# main.net
KiCad netlist of a schematic drawn in Altium Designer
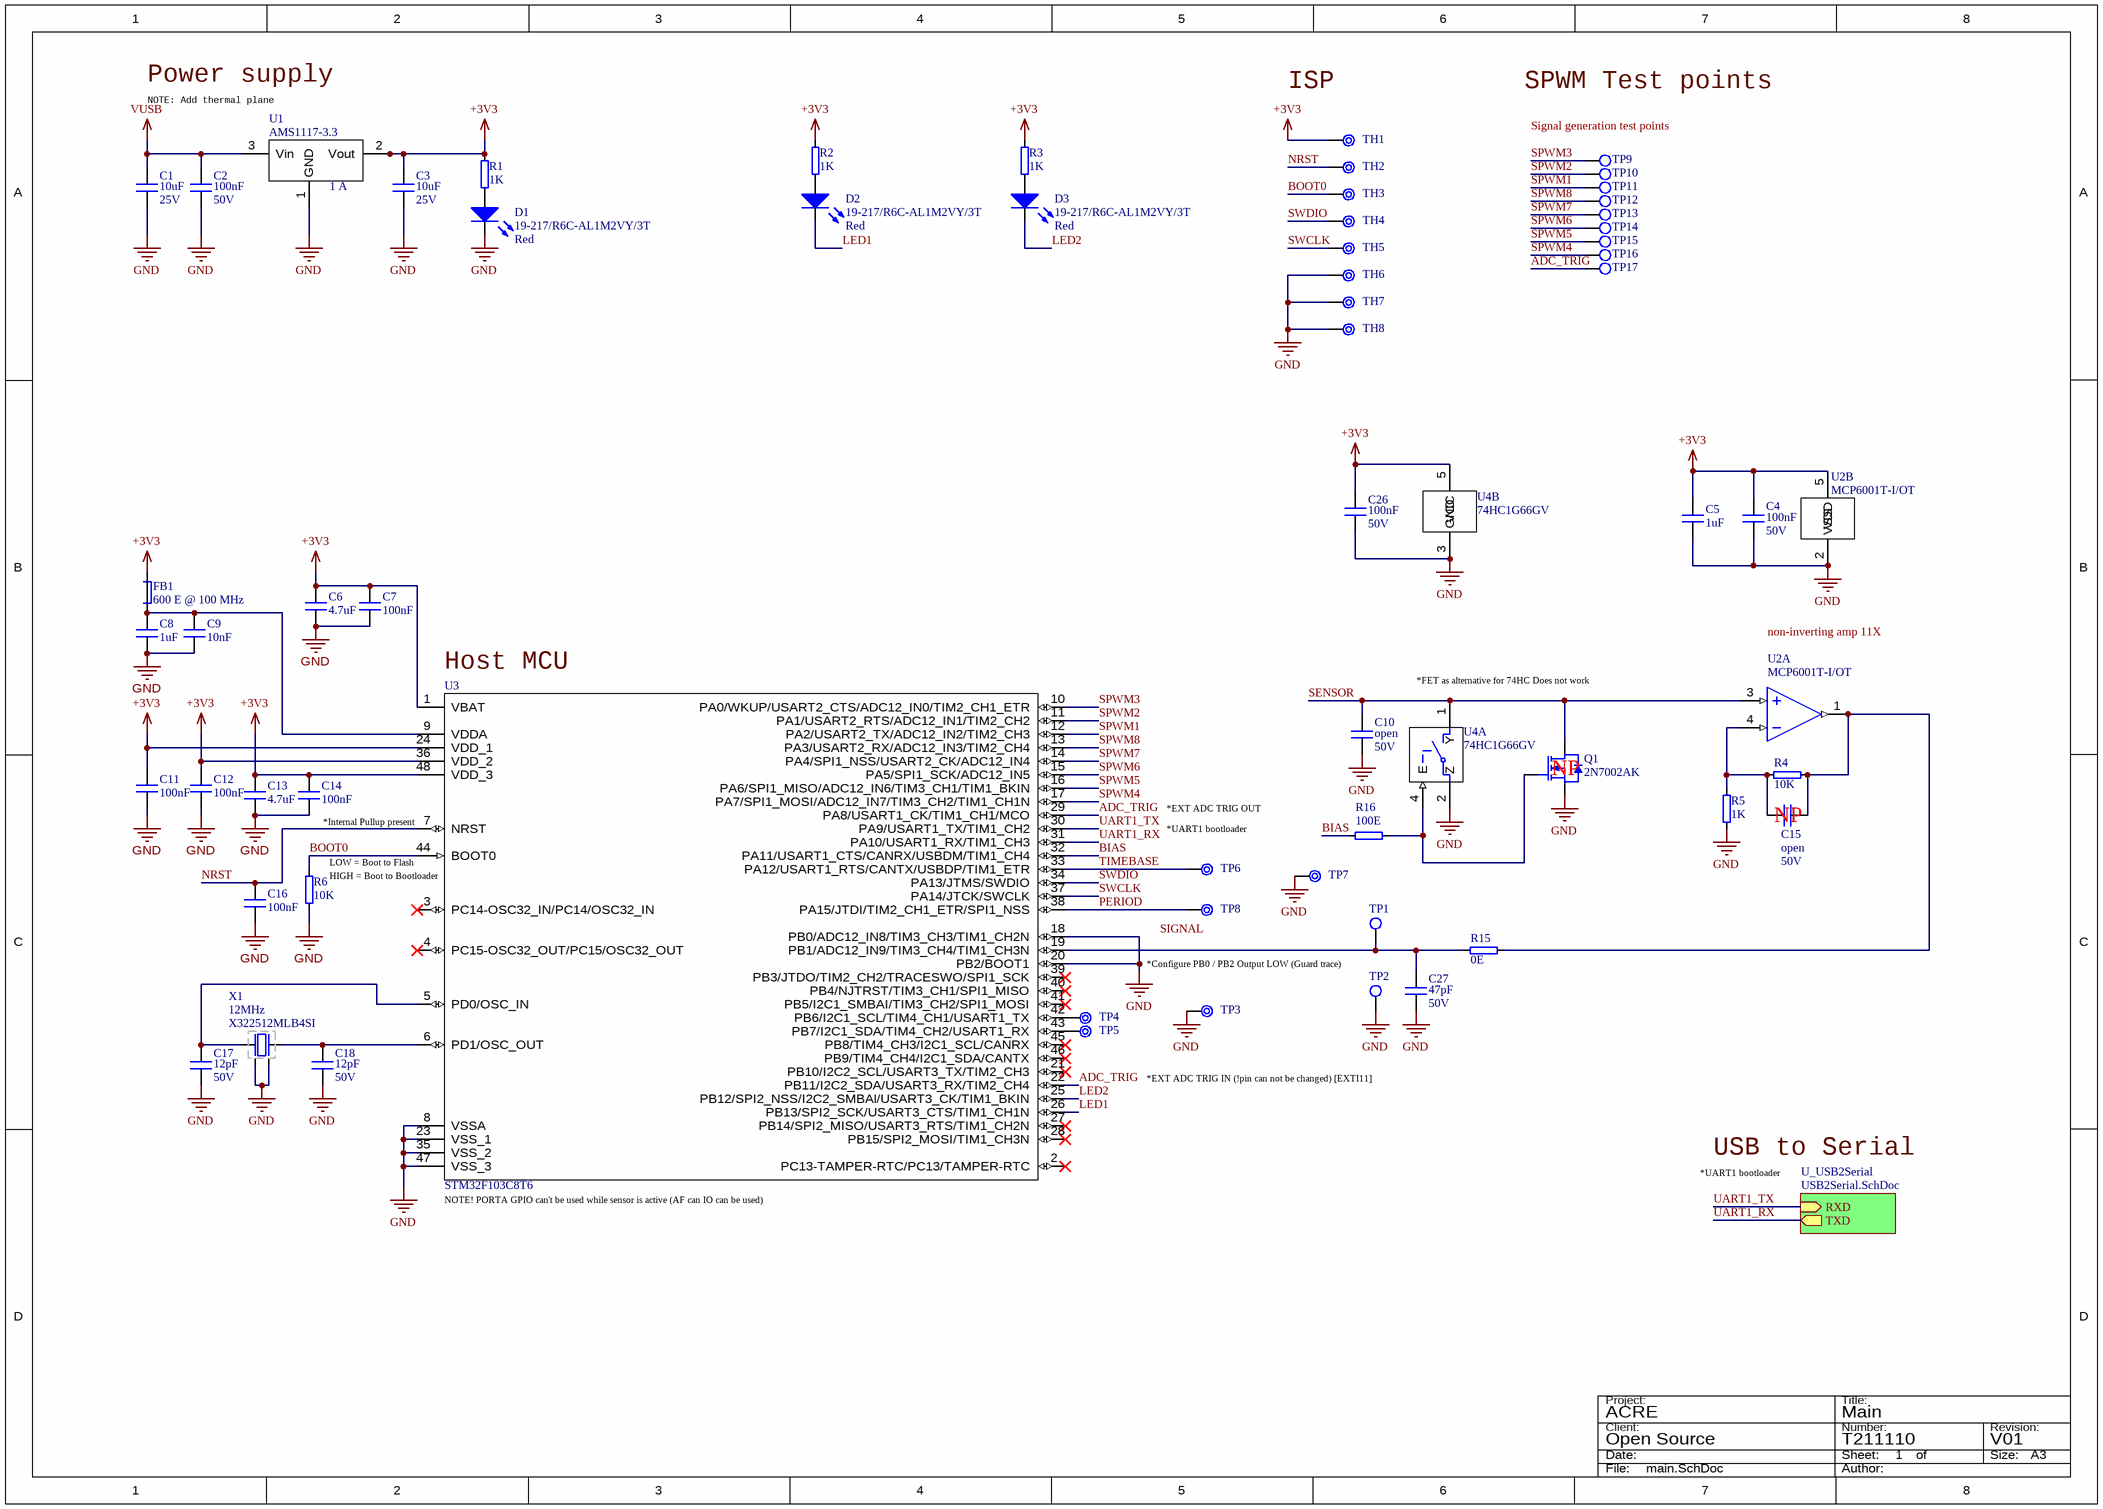
[diagram p0: main.SchDoc]

(export (version "E")
  (design (tool "Eeschema 10.0.6"))
  (components
    (comp (ref "C1")
      (value "10uF")
      (footprint "CAP 1206 3216 IPC MEDIUM")
      (description "10uF ±10% 25V X5R 1206 Multilayer Ceramic Capacitors MLCC - SMD/SMT RoHS")
      (fields
        (field (name "VOLTAGE") "25V")
        (field (name "PART NUMBER") "CL31A106KAHNNNE")
        (field (name "MANUFACTURER") "SAMSUNG")
      )
      (libsource (lib "P") (part "Capacitor"))
    )
    (comp (ref "C2")
      (value "100nF")
      (footprint "CAP 0603 1608 IPC MEDIUM")
      (description "100nF ±10% 50V X7R 0603 Multilayer Ceramic Capacitors MLCC - SMD/SMT RoHS")
      (fields
        (field (name "VOLTAGE") "50V")
        (field (name "PART NUMBER") "C0603B104K500NT")
        (field (name "MANUFACTURER") "TORCH")
      )
      (libsource (lib "P") (part "Capacitor"))
    )
    (comp (ref "C3")
      (value "10uF")
      (footprint "CAP 1206 3216 IPC MEDIUM")
      (description "10uF ±10% 25V X5R 1206 Multilayer Ceramic Capacitors MLCC - SMD/SMT RoHS")
      (fields
        (field (name "VOLTAGE") "25V")
        (field (name "PART NUMBER") "CL31A106KAHNNNE")
        (field (name "MANUFACTURER") "SAMSUNG")
      )
      (libsource (lib "P") (part "Capacitor"))
    )
    (comp (ref "C4")
      (value "100nF")
      (footprint "CAP 0603 1608 IPC MEDIUM")
      (description "100nF ±10% 50V X7R 0603 Multilayer Ceramic Capacitors MLCC - SMD/SMT RoHS")
      (fields
        (field (name "VOLTAGE") "50V")
        (field (name "PART NUMBER") "C0603B104K500NT")
        (field (name "MANUFACTURER") "TORCH")
      )
      (libsource (lib "P") (part "Capacitor"))
    )
    (comp (ref "C5")
      (value "1uF")
      (footprint "CAP 0603 1608 IPC MEDIUM")
      (description "Generic 0603 1608 Capacitor")
      (fields (field (name "VOLTAGE") "16V") (field (name "TOLERANCE") "20%"))
      (libsource (lib "P") (part "Capacitor"))
    )
    (comp (ref "C6")
      (value "4.7uF")
      (footprint "CAP 0603 1608 IPC MEDIUM")
      (description "4.7 µF, 25 V, 0603 [1608 Metric], ± 10%, X5R, GRM Series")
      (fields (field (name "VOLTAGE") "25V") (field (name "TOLERANCE") "10%"))
      (libsource (lib "P") (part "Capacitor"))
    )
    (comp (ref "C7")
      (value "100nF")
      (footprint "CAP 0603 1608 IPC MEDIUM")
      (description "100nF ±10% 50V X7R 0603 Multilayer Ceramic Capacitors MLCC - SMD/SMT RoHS")
      (fields (field (name "VOLTAGE") "50V") (field (name "TOLERANCE") "20%"))
      (libsource (lib "P") (part "Capacitor"))
    )
    (comp (ref "C8")
      (value "1uF")
      (footprint "CAP 0603 1608 IPC MEDIUM")
      (description "Generic 0603 1608 Capacitor")
      (fields (field (name "VOLTAGE") "16V") (field (name "TOLERANCE") "20%"))
      (libsource (lib "P") (part "Capacitor"))
    )
    (comp (ref "C9")
      (value "10nF")
      (footprint "CAP 0603 1608 IPC MEDIUM")
      (description "Generic 0603 1608 Capacitor")
      (fields (field (name "VOLTAGE") "50V") (field (name "TOLERANCE") "10%"))
      (libsource (lib "P") (part "Capacitor"))
    )
    (comp (ref "C10")
      (value "open")
      (footprint "CAP 0603 1608 IPC MEDIUM")
      (description "Capacitor 0603 1608 value undefined")
      (fields
        (field (name "VOLTAGE") "50V")
        (field (name "PART NUMBER") "x")
        (field (name "TOLERANCE") "10%")
      )
      (libsource (lib "P") (part "Capacitor"))
    )
    (comp (ref "C11")
      (value "100nF")
      (footprint "CAP 0603 1608 IPC MEDIUM")
      (description "100nF ±10% 50V X7R 0603 Multilayer Ceramic Capacitors MLCC - SMD/SMT RoHS")
      (fields (field (name "VOLTAGE") "50V") (field (name "TOLERANCE") "20%"))
      (libsource (lib "P") (part "Capacitor"))
    )
    (comp (ref "C12")
      (value "100nF")
      (footprint "CAP 0603 1608 IPC MEDIUM")
      (description "100nF ±10% 50V X7R 0603 Multilayer Ceramic Capacitors MLCC - SMD/SMT RoHS")
      (fields (field (name "VOLTAGE") "50V") (field (name "TOLERANCE") "20%"))
      (libsource (lib "P") (part "Capacitor"))
    )
    (comp (ref "C13")
      (value "4.7uF")
      (footprint "CAP 0603 1608 IPC MEDIUM")
      (description "4.7 µF, 25 V, 0603 [1608 Metric], ± 10%, X5R, GRM Series")
      (fields (field (name "VOLTAGE") "25V") (field (name "TOLERANCE") "10%"))
      (libsource (lib "P") (part "Capacitor"))
    )
    (comp (ref "C14")
      (value "100nF")
      (footprint "CAP 0603 1608 IPC MEDIUM")
      (description "100nF ±10% 50V X7R 0603 Multilayer Ceramic Capacitors MLCC - SMD/SMT RoHS")
      (fields (field (name "VOLTAGE") "50V") (field (name "TOLERANCE") "20%"))
      (libsource (lib "P") (part "Capacitor"))
    )
    (comp (ref "C15")
      (value "open")
      (footprint "CAP 0603 1608 IPC MEDIUM")
      (description "Capacitor 0603 1608 value undefined")
      (fields
        (field (name "VOLTAGE") "50V")
        (field (name "PART NUMBER") "x")
        (field (name "TOLERANCE") "10%")
      )
      (libsource (lib "P") (part "Capacitor"))
    )
    (comp (ref "C16")
      (value "100nF")
      (footprint "CAP 0603 1608 IPC MEDIUM")
      (description "100nF ±10% 50V X7R 0603 Multilayer Ceramic Capacitors MLCC - SMD/SMT RoHS")
      (fields (field (name "VOLTAGE") "50V") (field (name "TOLERANCE") "20%"))
      (libsource (lib "P") (part "Capacitor"))
    )
    (comp (ref "C17")
      (value "12pF")
      (footprint "CAP 0603 1608 IPC MEDIUM")
      (description "12pF ±5% 50V NP0 0603 Multilayer Ceramic Capacitors MLCC - SMD/SMT RoHS")
      (fields
        (field (name "VOLTAGE") "50V")
        (field (name "PART NUMBER") "CC0603JRNPO9BN120")
        (field (name "TOLERANCE") "5%")
      )
      (libsource (lib "P") (part "Capacitor"))
    )
    (comp (ref "C18")
      (value "12pF")
      (footprint "CAP 0603 1608 IPC MEDIUM")
      (description "12pF ±5% 50V NP0 0603 Multilayer Ceramic Capacitors MLCC - SMD/SMT RoHS")
      (fields
        (field (name "VOLTAGE") "50V")
        (field (name "PART NUMBER") "CC0603JRNPO9BN120")
        (field (name "TOLERANCE") "5%")
      )
      (libsource (lib "P") (part "Capacitor"))
    )
    (comp (ref "C26")
      (value "100nF")
      (footprint "CAP 0603 1608 IPC MEDIUM")
      (description "100nF ±10% 50V X7R 0603 Multilayer Ceramic Capacitors MLCC - SMD/SMT RoHS")
      (fields
        (field (name "VOLTAGE") "50V")
        (field (name "PART NUMBER") "C0603B104K500NT")
        (field (name "MANUFACTURER") "TORCH")
      )
      (libsource (lib "P") (part "Capacitor"))
    )
    (comp (ref "C27")
      (value "47pF")
      (footprint "CAP 0603 1608 IPC MEDIUM")
      (description "Generic 0603 1608 Capacitor")
      (fields
        (field (name "VOLTAGE") "50V")
        (field (name "PART NUMBER") "x")
        (field (name "TOLERANCE") "10%")
      )
      (libsource (lib "P") (part "Capacitor"))
    )
    (comp (ref "D1")
      (value "19-217/R6C-AL1M2VY/3T")
      (footprint "19-217 - EVERLIGHT")
      (description "Red 617.5~633.5nm 0603 Light Emitting Diodes (LED) RoHS")
      (fields (field (name "COLOUR") "Red") (field (name "MANUFACTURER") "EVERLIGHT"))
      (libsource (lib "P") (part "LED - [1A 2C]"))
    )
    (comp (ref "D2")
      (value "19-217/R6C-AL1M2VY/3T")
      (footprint "19-217 - EVERLIGHT")
      (description "Red 617.5~633.5nm 0603 Light Emitting Diodes (LED) RoHS")
      (fields (field (name "COLOUR") "Red") (field (name "MANUFACTURER") "EVERLIGHT"))
      (libsource (lib "P") (part "LED - [1A 2C]"))
    )
    (comp (ref "D3")
      (value "19-217/R6C-AL1M2VY/3T")
      (footprint "19-217 - EVERLIGHT")
      (description "Red 617.5~633.5nm 0603 Light Emitting Diodes (LED) RoHS")
      (fields (field (name "COLOUR") "Red") (field (name "MANUFACTURER") "EVERLIGHT"))
      (libsource (lib "P") (part "LED - [1A 2C]"))
    )
    (comp (ref "FB1")
      (value "600 E @ 100 MHz")
      (footprint "FB 0603 1608 IPC MEDIUM - Murata")
      (description "Ferrite Bead, 0603 [1608 Metric], 600 ohm, 500 mA, BLM18A Series, 0.38 ohm, ± 25%")
      (fields (field (name "PART NUMBER") "BLM18AG601SN1D") (field (name "MANUFACTURER") "MURATA"))
      (libsource (lib "P") (part "Ferrite bead"))
    )
    (comp (ref "Q1")
      (value "2N7002AK")
      (footprint "SOT23-3 IPC MEDIUM - NEXPERIA")
      (description "Power MOSFET, N Channel, 60 V, 190 mA, 3 ohm, SOT-23 TO-236AB")
      (fields (field (name "MANUFACTURER") "NEXPERIA"))
      (libsource (lib "P") (part "FET N-Channel [1G 2S 3D]"))
    )
    (comp (ref "R1")
      (value "1K")
      (footprint "RES 0603 1608 IPC MEDIUM")
      (description "1kΩ ±1% 0.1W ±100ppm/℃ 0603 Chip Resistor - Surface Mount RoHS")
      (fields (field (name "PART NUMBER") "RC0603FR-071KL") (field (name "MANUFACTURER") "YAGEO"))
      (libsource (lib "") (part "Resistor_1"))
    )
    (comp (ref "R2")
      (value "1K")
      (footprint "RES 0603 1608 IPC MEDIUM")
      (description "1kΩ ±1% 0.1W ±100ppm/℃ 0603 Chip Resistor - Surface Mount RoHS")
      (fields (field (name "PART NUMBER") "RC0603FR-071KL") (field (name "MANUFACTURER") "YAGEO"))
      (libsource (lib "") (part "Resistor_1"))
    )
    (comp (ref "R3")
      (value "1K")
      (footprint "RES 0603 1608 IPC MEDIUM")
      (description "1kΩ ±1% 0.1W ±100ppm/℃ 0603 Chip Resistor - Surface Mount RoHS")
      (fields (field (name "PART NUMBER") "RC0603FR-071KL") (field (name "MANUFACTURER") "YAGEO"))
      (libsource (lib "") (part "Resistor_1"))
    )
    (comp (ref "R4")
      (value "10K")
      (footprint "RES 0603 1608 IPC MEDIUM")
      (description "10kΩ ±1% 0.1W ±100ppm/℃ 0603 Chip Resistor - Surface Mount RoHS")
      (fields (field (name "PART NUMBER") "RC0603FR-0710KL") (field (name "MANUFACTURER") "YAGEO"))
      (libsource (lib "") (part "Resistor_2"))
    )
    (comp (ref "R5")
      (value "1K")
      (footprint "RES 0603 1608 IPC MEDIUM")
      (description "1kΩ ±1% 0.1W ±100ppm/℃ 0603 Chip Resistor - Surface Mount RoHS")
      (fields (field (name "PART NUMBER") "RC0603FR-071KL") (field (name "MANUFACTURER") "YAGEO"))
      (libsource (lib "") (part "Resistor_1"))
    )
    (comp (ref "R6")
      (value "10K")
      (footprint "RES 0603 1608 IPC MEDIUM")
      (description "10kΩ ±1% 0.1W ±100ppm/℃ 0603 Chip Resistor - Surface Mount RoHS")
      (fields (field (name "VOLTAGE") "75V") (field (name "POWER") "100mW"))
      (libsource (lib "P") (part "Resistor"))
    )
    (comp (ref "R15")
      (value "0E")
      (footprint "RES 0603 1608 IPC MEDIUM")
      (description "0Ω ±1.0% 1/10W Thick Film Resistors 75V -55℃~+155℃ 0603 Chip Resistor - Surface Mount RoHS")
      (fields (field (name "PART NUMBER") "RC0603FR-070RL") (field (name "MANUFACTURER") "YAGEO"))
      (libsource (lib "") (part "Resistor_2"))
    )
    (comp (ref "R16")
      (value "100E")
      (footprint "RES 0603 1608 IPC MEDIUM")
      (fields
        (field (name "PART NUMBER") "RC0603FR-07100RL")
        (field (name "VOLTAGE") "75V")
        (field (name "POWER") "100mW")
      )
      (libsource (lib "") (part "Resistor_2"))
    )
    (comp (ref "TH1")
      (value "~")
      (footprint "Test Header H1D1.6")
      (description "Octagonal THT H1D1.6mm test header")
      (libsource (lib "P") (part "Test Header"))
    )
    (comp (ref "TH2")
      (value "~")
      (footprint "Test Header H1D1.6")
      (description "Octagonal THT H1D1.6mm test header")
      (libsource (lib "P") (part "Test Header"))
    )
    (comp (ref "TH3")
      (value "~")
      (footprint "Test Header H1D1.6")
      (description "Octagonal THT H1D1.6mm test header")
      (libsource (lib "P") (part "Test Header"))
    )
    (comp (ref "TH4")
      (value "~")
      (footprint "Test Header H1D1.6")
      (description "Octagonal THT H1D1.6mm test header")
      (libsource (lib "P") (part "Test Header"))
    )
    (comp (ref "TH5")
      (value "~")
      (footprint "Test Header H1D1.6")
      (description "Octagonal THT H1D1.6mm test header")
      (libsource (lib "P") (part "Test Header"))
    )
    (comp (ref "TH6")
      (value "~")
      (footprint "Test Header H1D1.6")
      (description "Octagonal THT H1D1.6mm test header")
      (libsource (lib "P") (part "Test Header"))
    )
    (comp (ref "TH7")
      (value "~")
      (footprint "Test Header H1D1.6")
      (description "Octagonal THT H1D1.6mm test header")
      (libsource (lib "P") (part "Test Header"))
    )
    (comp (ref "TH8")
      (value "~")
      (footprint "Test Header H1D1.6")
      (description "Octagonal THT H1D1.6mm test header")
      (libsource (lib "P") (part "Test Header"))
    )
    (comp (ref "TP1")
      (value "0.8mm")
      (footprint "TEST POINT 0.8MM")
      (description "Round 0.8mm testpoint")
      (libsource (lib "P") (part "Test Point"))
    )
    (comp (ref "TP2")
      (value "0.8mm")
      (footprint "TEST POINT 0.8MM")
      (description "Round 0.8mm testpoint")
      (libsource (lib "P") (part "Test Point"))
    )
    (comp (ref "TP3")
      (value "~")
      (footprint "Test Header H1D1.6")
      (description "Octagonal THT H1D1.6mm test header")
      (libsource (lib "P") (part "Test Header"))
    )
    (comp (ref "TP4")
      (value "~")
      (footprint "Test Header H1D1.6")
      (description "Octagonal THT H1D1.6mm test header")
      (libsource (lib "P") (part "Test Header"))
    )
    (comp (ref "TP5")
      (value "~")
      (footprint "Test Header H1D1.6")
      (description "Octagonal THT H1D1.6mm test header")
      (libsource (lib "P") (part "Test Header"))
    )
    (comp (ref "TP6")
      (value "~")
      (footprint "Test Header H1D1.6")
      (description "Octagonal THT H1D1.6mm test header")
      (libsource (lib "P") (part "Test Header"))
    )
    (comp (ref "TP7")
      (value "~")
      (footprint "Test Header H1D1.6")
      (description "Octagonal THT H1D1.6mm test header")
      (libsource (lib "P") (part "Test Header"))
    )
    (comp (ref "TP8")
      (value "~")
      (footprint "Test Header H1D1.6")
      (description "Octagonal THT H1D1.6mm test header")
      (libsource (lib "P") (part "Test Header"))
    )
    (comp (ref "TP9")
      (value "0.5mm")
      (footprint "TEST POINT 0.5MM")
      (description "Round 0.5mm testpoint")
      (libsource (lib "P") (part "Test Point"))
    )
    (comp (ref "TP10")
      (value "0.5mm")
      (footprint "TEST POINT 0.5MM")
      (description "Round 0.5mm testpoint")
      (libsource (lib "P") (part "Test Point"))
    )
    (comp (ref "TP11")
      (value "0.5mm")
      (footprint "TEST POINT 0.5MM")
      (description "Round 0.5mm testpoint")
      (libsource (lib "P") (part "Test Point"))
    )
    (comp (ref "TP12")
      (value "0.5mm")
      (footprint "TEST POINT 0.5MM")
      (description "Round 0.5mm testpoint")
      (libsource (lib "P") (part "Test Point"))
    )
    (comp (ref "TP13")
      (value "0.5mm")
      (footprint "TEST POINT 0.5MM")
      (description "Round 0.5mm testpoint")
      (libsource (lib "P") (part "Test Point"))
    )
    (comp (ref "TP14")
      (value "0.5mm")
      (footprint "TEST POINT 0.5MM")
      (description "Round 0.5mm testpoint")
      (libsource (lib "P") (part "Test Point"))
    )
    (comp (ref "TP15")
      (value "0.5mm")
      (footprint "TEST POINT 0.5MM")
      (description "Round 0.5mm testpoint")
      (libsource (lib "P") (part "Test Point"))
    )
    (comp (ref "TP16")
      (value "0.5mm")
      (footprint "TEST POINT 0.5MM")
      (description "Round 0.5mm testpoint")
      (libsource (lib "P") (part "Test Point"))
    )
    (comp (ref "TP17")
      (value "0.5mm")
      (footprint "TEST POINT 0.5MM")
      (description "Round 0.5mm testpoint")
      (libsource (lib "P") (part "Test Point"))
    )
    (comp (ref "U1")
      (value "AMS1117-3.3")
      (footprint "SOT223 IPC MEDIUM - UMW")
      (description "LDO 3.3V 1A 18V")
      (fields (field (name "MANUFACTURER") "UMW") (field (name "IOUT") "1 A"))
      (libsource (lib "P") (part "AMS1117-3.3 - UMW"))
    )
    (comp (ref "U2")
      (value "MCP6001T-I/OT")
      (footprint "SOT23-5 IPC MEDIUM - MICROCHIP")
      (description "Operational Amplifier, Single, 1 Amplifier, 1 MHz, 0.6 V/µs, 1.8V to 6V, SOT-23, 5 Pins")
      (fields (field (name "MANUFACTURER") "MICROCHIP"))
      (libsource (lib "") (part "MCP6001T-I OT - MICROCHIP_1"))
    )
    (comp (ref "U3")
      (value "STM32F103C8T6")
      (footprint "LQFP48 IPC MEDIUM - STMICROELECTRONICS")
      (description "ARM Microcontroller, Motor Control, STM32 Family STM32F1 Series Microcontrollers, ARM Cortex-M3")
      (fields (field (name "MANUFACTURER") "STMICROELECTRONICS"))
      (libsource (lib "P") (part "STM32F103C8T6 - STMICROELECTRONICS"))
    )
    (comp (ref "U4")
      (value "74HC1G66GV")
      (footprint "SOT753 IPC MEDIUM - NEXPERIA")
      (description "Analogue Switch, SPST, 1 Channels, 50 ohm, 2V to 9V, TSOP, 5 Pins")
      (fields (field (name "MANUFACTURER") "NEXPERIA"))
      (libsource (lib "P") (part "74HC1G66GV - NEXPERIA"))
    )
    (comp (ref "X1")
      (value "X322512MLB4SI")
      (footprint "X322512MLB4SI - YXC")
      (description "12MHz ±10ppm 9pF 80Ω SMD-3225_4P Crystals RoHS")
      (fields (field (name "FREQUENCY") "12MHz") (field (name "MANUFACTURER") "YXC"))
      (libsource (lib "P") (part "Crystal in1 gnd2 out3 gnd4"))
    )
  )
  (nets
    (net (code "1") (name "+3V3") (class "Default")
      (node (ref "C11") (pin "1") (pinfunction "1_1") (pintype "passive"))
      (node (ref "C12") (pin "1") (pinfunction "1_1") (pintype "passive"))
      (node (ref "C13") (pin "1") (pinfunction "1_1") (pintype "passive"))
      (node (ref "C14") (pin "1") (pinfunction "1_1") (pintype "passive"))
      (node (ref "C26") (pin "1") (pinfunction "1_1") (pintype "passive"))
      (node (ref "C3") (pin "1") (pinfunction "1_1") (pintype "passive"))
      (node (ref "C4") (pin "1") (pinfunction "1_1") (pintype "passive"))
      (node (ref "C5") (pin "1") (pinfunction "1_1") (pintype "passive"))
      (node (ref "C6") (pin "1") (pinfunction "1_1") (pintype "passive"))
      (node (ref "C7") (pin "1") (pinfunction "1_1") (pintype "passive"))
      (node (ref "FB1") (pin "1") (pinfunction "1_1") (pintype "passive"))
      (node (ref "R1") (pin "2") (pinfunction "2_2") (pintype "passive"))
      (node (ref "R2") (pin "2") (pinfunction "2_2") (pintype "passive"))
      (node (ref "R3") (pin "2") (pinfunction "2_2") (pintype "passive"))
      (node (ref "TH1") (pin "1") (pintype "passive"))
      (node (ref "U1") (pin "2") (pinfunction "Vout_2") (pintype "power_in"))
      (node (ref "U1") (pin "4") (pinfunction "Vout_4") (pintype "power_in"))
      (node (ref "U2") (pin "5") (pinfunction "VDD_5") (pintype "power_in"))
      (node (ref "U3") (pin "1") (pinfunction "VBAT_1") (pintype "power_in"))
      (node (ref "U3") (pin "24") (pinfunction "VDD_1_24") (pintype "power_in"))
      (node (ref "U3") (pin "36") (pinfunction "VDD_2_36") (pintype "power_in"))
      (node (ref "U3") (pin "48") (pinfunction "VDD_3_48") (pintype "power_in"))
      (node (ref "U4") (pin "5") (pinfunction "VCC_5") (pintype "power_in"))
    )
    (net (code "2") (name "/ADC_TRIG") (class "Default")
      (node (ref "TP17") (pin "1") (pintype "passive"))
      (node (ref "U3") (pin "22") (pinfunction "PB11/I2C2_SDA/USART3_RX/TIM2_CH4_22") (pintype "bidirectional"))
      (node (ref "U3") (pin "29") (pinfunction "PA8/USART1_CK/TIM1_CH1/MCO_29") (pintype "bidirectional"))
    )
    (net (code "3") (name "/BIAS") (class "Default")
      (node (ref "R16") (pin "1") (pinfunction "1_1") (pintype "passive"))
      (node (ref "U3") (pin "32") (pinfunction "PA11/USART1_CTS/CANRX/USBDM/TIM1_CH4_32") (pintype "bidirectional"))
    )
    (net (code "4") (name "/BOOT0") (class "Default")
      (node (ref "R6") (pin "1") (pinfunction "1_1") (pintype "passive"))
      (node (ref "TH3") (pin "1") (pintype "passive"))
      (node (ref "U3") (pin "44") (pinfunction "BOOT0_44") (pintype "input"))
    )
    (net (code "5") (name "/LED1") (class "Default")
      (node (ref "D2") (pin "2") (pinfunction "C_2") (pintype "passive"))
      (node (ref "U3") (pin "26") (pinfunction "PB13/SPI2_SCK/USART3_CTS/TIM1_CH1N_26") (pintype "bidirectional"))
    )
    (net (code "6") (name "/LED2") (class "Default")
      (node (ref "D3") (pin "2") (pinfunction "C_2") (pintype "passive"))
      (node (ref "U3") (pin "25") (pinfunction "PB12/SPI2_NSS/I2C2_SMBAl/USART3_CK/TIM1_BKIN_25") (pintype "bidirectional"))
    )
    (net (code "7") (name "/NRST") (class "Default")
      (node (ref "C16") (pin "1") (pinfunction "1_1") (pintype "passive"))
      (node (ref "TH2") (pin "1") (pintype "passive"))
      (node (ref "U3") (pin "7") (pinfunction "NRST_7") (pintype "bidirectional"))
    )
    (net (code "8") (name "/PERIOD") (class "Default")
      (node (ref "TP8") (pin "1") (pintype "passive"))
      (node (ref "U3") (pin "38") (pinfunction "PA15/JTDI/TIM2_CH1_ETR/SPI1_NSS_38") (pintype "bidirectional"))
    )
    (net (code "9") (name "/SENSOR") (class "Default")
      (node (ref "C10") (pin "1") (pinfunction "1_1") (pintype "passive"))
      (node (ref "Q1") (pin "3") (pinfunction "D_3") (pintype "passive"))
      (node (ref "U2") (pin "3") (pinfunction "VIN+_3") (pintype "input"))
      (node (ref "U4") (pin "1") (pinfunction "Y_1") (pintype "passive"))
    )
    (net (code "11") (name "/SPWM1") (class "Default")
      (node (ref "TP11") (pin "1") (pintype "passive"))
      (node (ref "U3") (pin "12") (pinfunction "PA2/USART2_TX/ADC12_IN2/TIM2_CH3_12") (pintype "bidirectional"))
    )
    (net (code "12") (name "/SPWM2") (class "Default")
      (node (ref "TP10") (pin "1") (pintype "passive"))
      (node (ref "U3") (pin "11") (pinfunction "PA1/USART2_RTS/ADC12_IN1/TIM2_CH2_11") (pintype "bidirectional"))
    )
    (net (code "13") (name "/SPWM3") (class "Default")
      (node (ref "TP9") (pin "1") (pintype "passive"))
      (node (ref "U3") (pin "10") (pinfunction "PA0/WKUP/USART2_CTS/ADC12_IN0/TIM2_CH1_ETR_10") (pintype "bidirectional"))
    )
    (net (code "14") (name "/SPWM4") (class "Default")
      (node (ref "TP16") (pin "1") (pintype "passive"))
      (node (ref "U3") (pin "17") (pinfunction "PA7/SPI1_MOSI/ADC12_IN7/TIM3_CH2/TIM1_CH1N_17") (pintype "bidirectional"))
    )
    (net (code "15") (name "/SPWM5") (class "Default")
      (node (ref "TP15") (pin "1") (pintype "passive"))
      (node (ref "U3") (pin "16") (pinfunction "PA6/SPI1_MISO/ADC12_IN6/TIM3_CH1/TIM1_BKIN_16") (pintype "bidirectional"))
    )
    (net (code "16") (name "/SPWM6") (class "Default")
      (node (ref "TP14") (pin "1") (pintype "passive"))
      (node (ref "U3") (pin "15") (pinfunction "PA5/SPI1_SCK/ADC12_IN5_15") (pintype "bidirectional"))
    )
    (net (code "17") (name "/SPWM7") (class "Default")
      (node (ref "TP13") (pin "1") (pintype "passive"))
      (node (ref "U3") (pin "14") (pinfunction "PA4/SPI1_NSS/USART2_CK/ADC12_IN4_14") (pintype "bidirectional"))
    )
    (net (code "18") (name "/SPWM8") (class "Default")
      (node (ref "TP12") (pin "1") (pintype "passive"))
      (node (ref "U3") (pin "13") (pinfunction "PA3/USART2_RX/ADC12_IN3/TIM2_CH4_13") (pintype "bidirectional"))
    )
    (net (code "19") (name "/SWCLK") (class "Default")
      (node (ref "TH5") (pin "1") (pintype "passive"))
      (node (ref "U3") (pin "37") (pinfunction "PA14/JTCK/SWCLK_37") (pintype "bidirectional"))
    )
    (net (code "20") (name "/SWDIO") (class "Default")
      (node (ref "TH4") (pin "1") (pintype "passive"))
      (node (ref "U3") (pin "34") (pinfunction "PA13/JTMS/SWDIO_34") (pintype "bidirectional"))
    )
    (net (code "21") (name "/TIMEBASE") (class "Default")
      (node (ref "TP6") (pin "1") (pintype "passive"))
      (node (ref "U3") (pin "33") (pinfunction "PA12/USART1_RTS/CANTX/USBDP/TIM1_ETR_33") (pintype "bidirectional"))
    )
    (net (code "22") (name "/UART1_RX") (class "Default")
      (node (ref "U3") (pin "31") (pinfunction "PA10/USART1_RX/TIM1_CH3_31") (pintype "bidirectional"))
    )
    (net (code "23") (name "/UART1_TX") (class "Default")
      (node (ref "U3") (pin "30") (pinfunction "PA9/USART1_TX/TIM1_CH2_30") (pintype "bidirectional"))
    )
    (net (code "24") (name "GND") (class "Default")
      (node (ref "C1") (pin "2") (pinfunction "2_2") (pintype "passive"))
      (node (ref "C10") (pin "2") (pinfunction "2_2") (pintype "passive"))
      (node (ref "C11") (pin "2") (pinfunction "2_2") (pintype "passive"))
      (node (ref "C12") (pin "2") (pinfunction "2_2") (pintype "passive"))
      (node (ref "C13") (pin "2") (pinfunction "2_2") (pintype "passive"))
      (node (ref "C14") (pin "2") (pinfunction "2_2") (pintype "passive"))
      (node (ref "C16") (pin "2") (pinfunction "2_2") (pintype "passive"))
      (node (ref "C17") (pin "2") (pinfunction "2_2") (pintype "passive"))
      (node (ref "C18") (pin "2") (pinfunction "2_2") (pintype "passive"))
      (node (ref "C2") (pin "2") (pinfunction "2_2") (pintype "passive"))
      (node (ref "C26") (pin "2") (pinfunction "2_2") (pintype "passive"))
      (node (ref "C27") (pin "2") (pinfunction "2_2") (pintype "passive"))
      (node (ref "C3") (pin "2") (pinfunction "2_2") (pintype "passive"))
      (node (ref "C4") (pin "2") (pinfunction "2_2") (pintype "passive"))
      (node (ref "C5") (pin "2") (pinfunction "2_2") (pintype "passive"))
      (node (ref "C6") (pin "2") (pinfunction "2_2") (pintype "passive"))
      (node (ref "C7") (pin "2") (pinfunction "2_2") (pintype "passive"))
      (node (ref "C8") (pin "2") (pinfunction "2_2") (pintype "passive"))
      (node (ref "C9") (pin "2") (pinfunction "2_2") (pintype "passive"))
      (node (ref "D1") (pin "2") (pinfunction "C_2") (pintype "passive"))
      (node (ref "Q1") (pin "2") (pinfunction "S_2") (pintype "passive"))
      (node (ref "R5") (pin "1") (pinfunction "1_1") (pintype "passive"))
      (node (ref "R6") (pin "2") (pinfunction "2_2") (pintype "passive"))
      (node (ref "TH6") (pin "1") (pintype "passive"))
      (node (ref "TH7") (pin "1") (pintype "passive"))
      (node (ref "TH8") (pin "1") (pintype "passive"))
      (node (ref "TP2") (pin "1") (pintype "passive"))
      (node (ref "TP3") (pin "1") (pintype "passive"))
      (node (ref "TP7") (pin "1") (pintype "passive"))
      (node (ref "U1") (pin "1") (pinfunction "GND_1") (pintype "power_in"))
      (node (ref "U2") (pin "2") (pinfunction "VSS_2") (pintype "power_in"))
      (node (ref "U3") (pin "18") (pinfunction "PB0/ADC12_IN8/TIM3_CH3/TIM1_CH2N_18") (pintype "bidirectional"))
      (node (ref "U3") (pin "20") (pinfunction "PB2/BOOT1_20") (pintype "bidirectional"))
      (node (ref "U3") (pin "23") (pinfunction "VSS_1_23") (pintype "power_in"))
      (node (ref "U3") (pin "35") (pinfunction "VSS_2_35") (pintype "power_in"))
      (node (ref "U3") (pin "47") (pinfunction "VSS_3_47") (pintype "power_in"))
      (node (ref "U3") (pin "8") (pinfunction "VSSA_8") (pintype "power_in"))
      (node (ref "U4") (pin "2") (pinfunction "Z_2") (pintype "passive"))
      (node (ref "U4") (pin "3") (pinfunction "GND_3") (pintype "power_in"))
      (node (ref "X1") (pin "2") (pinfunction "GND_2") (pintype "passive"))
      (node (ref "X1") (pin "4") (pinfunction "GND_4") (pintype "passive"))
    )
    (net (code "25") (name "Net-(D1-A)") (class "Default")
      (node (ref "D1") (pin "1") (pinfunction "A_1") (pintype "passive"))
      (node (ref "R1") (pin "1") (pinfunction "1_1") (pintype "passive"))
    )
    (net (code "26") (name "Net-(D2-A)") (class "Default")
      (node (ref "D2") (pin "1") (pinfunction "A_1") (pintype "passive"))
      (node (ref "R2") (pin "1") (pinfunction "1_1") (pintype "passive"))
    )
    (net (code "27") (name "Net-(D3-A)") (class "Default")
      (node (ref "D3") (pin "1") (pinfunction "A_1") (pintype "passive"))
      (node (ref "R3") (pin "1") (pinfunction "1_1") (pintype "passive"))
    )
    (net (code "28") (name "Net-(Q1-G)") (class "Default")
      (node (ref "Q1") (pin "1") (pinfunction "G_1") (pintype "passive"))
      (node (ref "R16") (pin "2") (pinfunction "2_2") (pintype "passive"))
      (node (ref "U4") (pin "4") (pinfunction "E_4") (pintype "input"))
    )
    (net (code "29") (name "Net-(U2A-VIN-)") (class "Default")
      (node (ref "C15") (pin "1") (pinfunction "1_1") (pintype "passive"))
      (node (ref "R4") (pin "1") (pinfunction "1_1") (pintype "passive"))
      (node (ref "R5") (pin "2") (pinfunction "2_2") (pintype "passive"))
      (node (ref "U2") (pin "4") (pinfunction "VIN-_4") (pintype "input"))
    )
    (net (code "30") (name "Net-(U2A-VOUT)") (class "Default")
      (node (ref "C15") (pin "2") (pinfunction "2_2") (pintype "passive"))
      (node (ref "R15") (pin "2") (pinfunction "2_2") (pintype "passive"))
      (node (ref "R4") (pin "2") (pinfunction "2_2") (pintype "passive"))
      (node (ref "U2") (pin "1") (pinfunction "VOUT_1") (pintype "output"))
    )
    (net (code "31") (name "Net-(U3-PB1{slash}ADC12_IN9{slash}TIM3_CH4{slash}TIM1_CH3N)") (class "Default")
      (node (ref "C27") (pin "1") (pinfunction "1_1") (pintype "passive"))
      (node (ref "R15") (pin "1") (pinfunction "1_1") (pintype "passive"))
      (node (ref "TP1") (pin "1") (pintype "passive"))
      (node (ref "U3") (pin "19") (pinfunction "PB1/ADC12_IN9/TIM3_CH4/TIM1_CH3N_19") (pintype "bidirectional"))
    )
    (net (code "32") (name "Net-(U3-PB6{slash}I2C1_SCL{slash}TIM4_CH1{slash}USART1_TX)") (class "Default")
      (node (ref "TP4") (pin "1") (pintype "passive"))
      (node (ref "U3") (pin "42") (pinfunction "PB6/I2C1_SCL/TIM4_CH1/USART1_TX_42") (pintype "bidirectional"))
    )
    (net (code "33") (name "Net-(U3-PB7{slash}I2C1_SDA{slash}TIM4_CH2{slash}USART1_RX)") (class "Default")
      (node (ref "TP5") (pin "1") (pintype "passive"))
      (node (ref "U3") (pin "43") (pinfunction "PB7/I2C1_SDA/TIM4_CH2/USART1_RX_43") (pintype "bidirectional"))
    )
    (net (code "34") (name "Net-(U3-PD0{slash}OSC_IN)") (class "Default")
      (node (ref "C17") (pin "1") (pinfunction "1_1") (pintype "passive"))
      (node (ref "U3") (pin "5") (pinfunction "PD0/OSC_IN_5") (pintype "bidirectional"))
      (node (ref "X1") (pin "1") (pinfunction "in_1") (pintype "passive"))
    )
    (net (code "35") (name "Net-(U3-PD1{slash}OSC_OUT)") (class "Default")
      (node (ref "C18") (pin "1") (pinfunction "1_1") (pintype "passive"))
      (node (ref "U3") (pin "6") (pinfunction "PD1/OSC_OUT_6") (pintype "bidirectional"))
      (node (ref "X1") (pin "3") (pinfunction "out_3") (pintype "passive"))
    )
    (net (code "36") (name "Net-(U3-VDDA)") (class "Default")
      (node (ref "C8") (pin "1") (pinfunction "1_1") (pintype "passive"))
      (node (ref "C9") (pin "1") (pinfunction "1_1") (pintype "passive"))
      (node (ref "FB1") (pin "2") (pinfunction "2_2") (pintype "passive"))
      (node (ref "U3") (pin "9") (pinfunction "VDDA_9") (pintype "power_in"))
    )
    (net (code "37") (name "VUSB") (class "Default")
      (node (ref "C1") (pin "1") (pinfunction "1_1") (pintype "passive"))
      (node (ref "C2") (pin "1") (pinfunction "1_1") (pintype "passive"))
      (node (ref "U1") (pin "3") (pinfunction "Vin_3") (pintype "power_in"))
    )
    (net (code "38") (name "unconnected-(U3-PB3{slash}JTDO{slash}TIM2_CH2{slash}TRACESWO{slash}SPI1_SCK-Pad39)") (class "Default")
      (node (ref "U3") (pin "39") (pinfunction "PB3/JTDO/TIM2_CH2/TRACESWO/SPI1_SCK_39") (pintype "bidirectional+no_connect"))
    )
    (net (code "39") (name "unconnected-(U3-PB4{slash}NJTRST{slash}TIM3_CH1{slash}SPI1_MISO-Pad40)") (class "Default")
      (node (ref "U3") (pin "40") (pinfunction "PB4/NJTRST/TIM3_CH1/SPI1_MISO_40") (pintype "bidirectional+no_connect"))
    )
    (net (code "40") (name "unconnected-(U3-PB5{slash}I2C1_SMBAI{slash}TIM3_CH2{slash}SPI1_MOSI-Pad41)") (class "Default")
      (node (ref "U3") (pin "41") (pinfunction "PB5/I2C1_SMBAI/TIM3_CH2/SPI1_MOSI_41") (pintype "bidirectional+no_connect"))
    )
    (net (code "41") (name "unconnected-(U3-PB8{slash}TIM4_CH3{slash}I2C1_SCL{slash}CANRX-Pad45)") (class "Default")
      (node (ref "U3") (pin "45") (pinfunction "PB8/TIM4_CH3/I2C1_SCL/CANRX_45") (pintype "bidirectional+no_connect"))
    )
    (net (code "42") (name "unconnected-(U3-PB9{slash}TIM4_CH4{slash}I2C1_SDA{slash}CANTX-Pad46)") (class "Default")
      (node (ref "U3") (pin "46") (pinfunction "PB9/TIM4_CH4/I2C1_SDA/CANTX_46") (pintype "bidirectional+no_connect"))
    )
    (net (code "43") (name "unconnected-(U3-PB10{slash}I2C2_SCL{slash}USART3_TX{slash}TIM2_CH3-Pad21)") (class "Default")
      (node (ref "U3") (pin "21") (pinfunction "PB10/I2C2_SCL/USART3_TX/TIM2_CH3_21") (pintype "bidirectional+no_connect"))
    )
    (net (code "44") (name "unconnected-(U3-PB14{slash}SPI2_MISO{slash}USART3_RTS{slash}TIM1_CH2N-Pad27)") (class "Default")
      (node (ref "U3") (pin "27") (pinfunction "PB14/SPI2_MISO/USART3_RTS/TIM1_CH2N_27") (pintype "bidirectional+no_connect"))
    )
    (net (code "45") (name "unconnected-(U3-PB15{slash}SPI2_MOSI{slash}TIM1_CH3N-Pad28)") (class "Default")
      (node (ref "U3") (pin "28") (pinfunction "PB15/SPI2_MOSI/TIM1_CH3N_28") (pintype "bidirectional+no_connect"))
    )
    (net (code "46") (name "unconnected-(U3-PC13-TAMPER-RTC{slash}PC13{slash}TAMPER-RTC-Pad2)") (class "Default")
      (node (ref "U3") (pin "2") (pinfunction "PC13-TAMPER-RTC/PC13/TAMPER-RTC_2") (pintype "bidirectional+no_connect"))
    )
    (net (code "47") (name "unconnected-(U3-PC14-OSC32_IN{slash}PC14{slash}OSC32_IN-Pad3)") (class "Default")
      (node (ref "U3") (pin "3") (pinfunction "PC14-OSC32_IN/PC14/OSC32_IN_3") (pintype "bidirectional+no_connect"))
    )
    (net (code "48") (name "unconnected-(U3-PC15-OSC32_OUT{slash}PC15{slash}OSC32_OUT-Pad4)") (class "Default")
      (node (ref "U3") (pin "4") (pinfunction "PC15-OSC32_OUT/PC15/OSC32_OUT_4") (pintype "bidirectional+no_connect"))
    )
  )
)
